# Vdd.net
KiCad netlist of a schematic drawn in Altium Designer
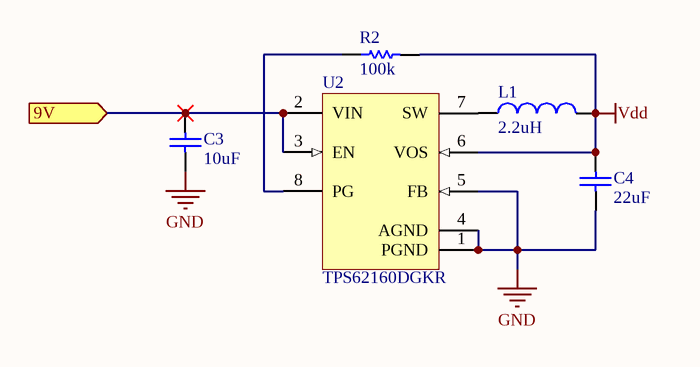
[diagram p0: Vdd.SchDoc]

(export (version "E")
  (design (tool "Eeschema 10.0.6"))
  (components
    (comp (ref "C3")
      (value "10uF")
      (footprint "C1206")
      (description "Capacitor")
      (fields (field (name "Comment") "Cap") (field (name "PUBLISHER") "Altium Limited"))
      (libsource (lib "Miscellaneous Devices") (part "Cap"))
    )
    (comp (ref "C4")
      (value "22uF")
      (footprint "C1206")
      (description "Capacitor")
      (fields (field (name "Comment") "Cap") (field (name "PUBLISHER") "Altium Limited"))
      (libsource (lib "Miscellaneous Devices") (part "Cap"))
    )
    (comp (ref "L1")
      (value "2.2uH")
      (footprint "1608[0603]")
      (description "Inductor")
      (fields (field (name "PUBLISHER") "Altium Limited"))
      (libsource (lib "Miscellaneous Devices") (part "Inductor"))
    )
    (comp (ref "R2")
      (value "100k")
      (footprint "C1206")
      (description "Resistor")
      (fields (field (name "Comment") "Res1") (field (name "PUBLISHER") "Altium Limited"))
      (libsource (lib "Miscellaneous Devices") (part "Res1"))
    )
    (comp (ref "U2")
      (value "TPS62160DGKR")
      (footprint "DGK8_N")
      (fields (field (name "MANUFACTURER") "Texas Instruments"))
      (libsource (lib "TI Power Management Step-Down Regulator") (part "TPS62160DGKR"))
    )
  )
  (nets
    (net (code "1") (name "/9V") (class "Default")
      (node (ref "C3") (pin "2") (pinfunction "2_2") (pintype "passive"))
      (node (ref "U2") (pin "2") (pinfunction "VIN_2") (pintype "power_in"))
      (node (ref "U2") (pin "3") (pinfunction "EN_3") (pintype "input"))
    )
    (net (code "2") (name "GND") (class "Default")
      (node (ref "C3") (pin "1") (pinfunction "1_1") (pintype "passive"))
      (node (ref "C4") (pin "1") (pinfunction "1_1") (pintype "passive"))
      (node (ref "U2") (pin "1") (pinfunction "PGND_1") (pintype "power_in"))
      (node (ref "U2") (pin "4") (pinfunction "AGND_4") (pintype "power_in"))
      (node (ref "U2") (pin "5") (pinfunction "FB_5") (pintype "input"))
    )
    (net (code "3") (name "Net-(U2-PG)") (class "Default")
      (node (ref "R2") (pin "1") (pinfunction "1_1") (pintype "passive"))
      (node (ref "U2") (pin "8") (pinfunction "PG_8") (pintype "tri_state"))
    )
    (net (code "4") (name "Net-(U2-SW)") (class "Default")
      (node (ref "L1") (pin "1") (pinfunction "1_1") (pintype "passive"))
      (node (ref "U2") (pin "7") (pinfunction "SW_7") (pintype "power_in"))
    )
    (net (code "5") (name "Vdd") (class "Default")
      (node (ref "C4") (pin "2") (pinfunction "2_2") (pintype "passive"))
      (node (ref "L1") (pin "2") (pinfunction "2_2") (pintype "passive"))
      (node (ref "R2") (pin "2") (pinfunction "2_2") (pintype "passive"))
      (node (ref "U2") (pin "6") (pinfunction "VOS_6") (pintype "input"))
    )
  )
)
